# ble2mqtt.net
KiCad netlist of a schematic drawn in EAGLE
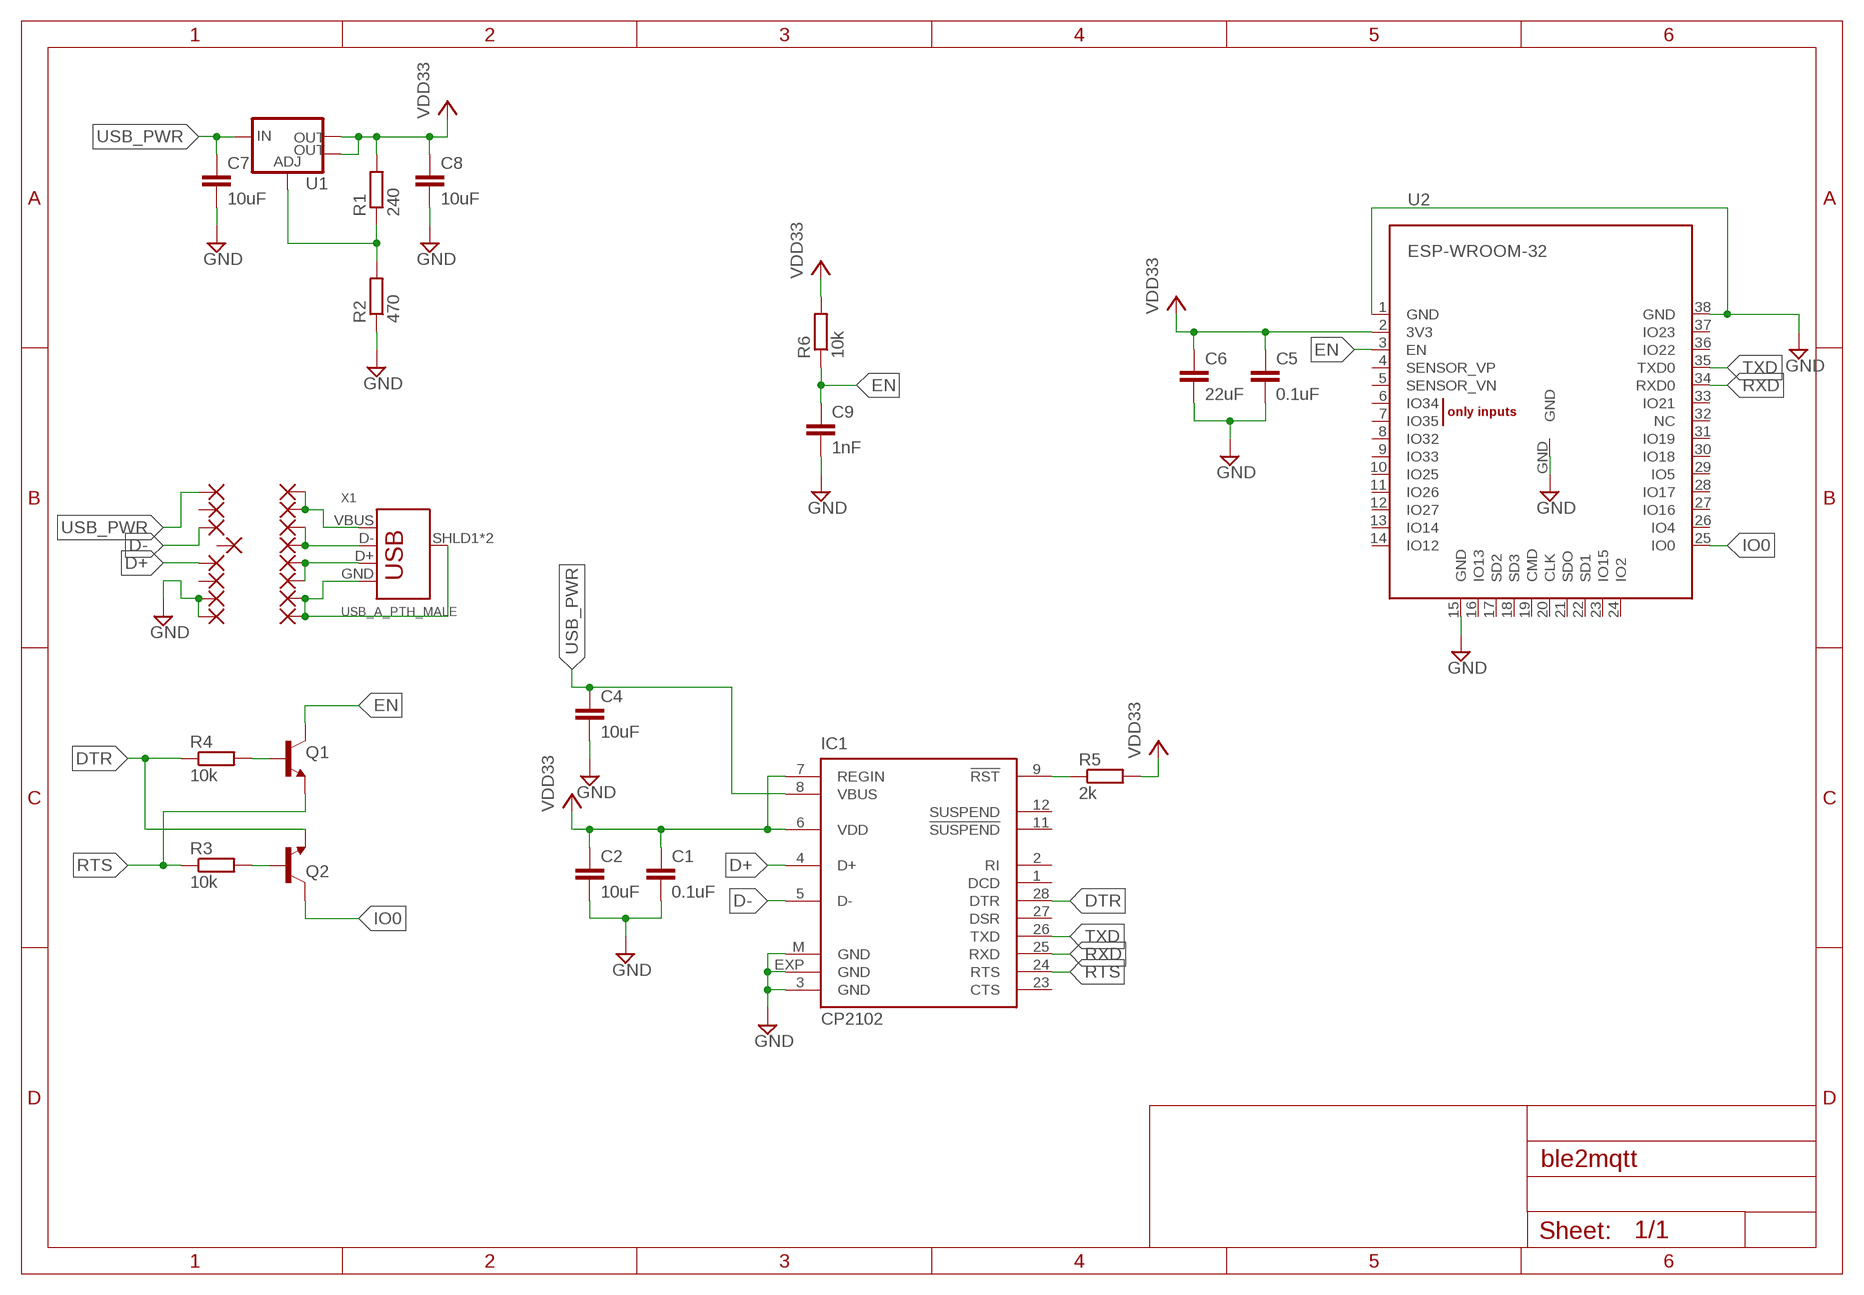
[diagram p0: schematic, sheet 1]

(export (version "E")
  (design (tool "Eeschema 10.0.6"))
  (components
    (comp (ref "C1")
      (value "0.1uF")
      (footprint "eagle-import:0402")
      (libsource (lib "eagle-import") (part "CAPACITOR_0402"))
    )
    (comp (ref "C2")
      (value "10uF")
      (footprint "eagle-import:0402")
      (libsource (lib "eagle-import") (part "CAPACITOR_0402"))
    )
    (comp (ref "C4")
      (value "10uF")
      (footprint "eagle-import:0402")
      (libsource (lib "eagle-import") (part "CAPACITOR_0402"))
    )
    (comp (ref "C5")
      (value "0.1uF")
      (footprint "eagle-import:0402")
      (libsource (lib "eagle-import") (part "CAPACITOR_0402"))
    )
    (comp (ref "C6")
      (value "22uF")
      (footprint "eagle-import:0402")
      (libsource (lib "eagle-import") (part "CAPACITOR_0402"))
    )
    (comp (ref "C7")
      (value "10uF")
      (footprint "eagle-import:0402")
      (libsource (lib "eagle-import") (part "CAPACITOR_0402"))
    )
    (comp (ref "C8")
      (value "10uF")
      (footprint "eagle-import:0402")
      (libsource (lib "eagle-import") (part "CAPACITOR_0402"))
    )
    (comp (ref "C9")
      (value "1nF")
      (footprint "eagle-import:0402")
      (libsource (lib "eagle-import") (part "CAPACITOR_0402"))
    )
    (comp (ref "IC1")
      (value "CP2102")
      (footprint "eagle-import:MLP28")
      (fields (field (name "MF") "FARNELL") (field (name "MPN") "CP2102-GM"))
      (libsource (lib "eagle-import") (part "CP2102"))
    )
    (comp (ref "PAD1")
      (value "WIREPADSMD1,27-254")
      (footprint "eagle-import:SMD1,27-2,54")
      (libsource (lib "eagle-import") (part "WIREPADSMD1,27-254"))
    )
    (comp (ref "PAD2")
      (value "WIREPADSMD1,27-254")
      (footprint "eagle-import:SMD1,27-2,54")
      (libsource (lib "eagle-import") (part "WIREPADSMD1,27-254"))
    )
    (comp (ref "PAD3")
      (value "WIREPADSMD1,27-254")
      (footprint "eagle-import:SMD1,27-2,54")
      (libsource (lib "eagle-import") (part "WIREPADSMD1,27-254"))
    )
    (comp (ref "PAD4")
      (value "WIREPADSMD1,27-254")
      (footprint "eagle-import:SMD1,27-2,54")
      (libsource (lib "eagle-import") (part "WIREPADSMD1,27-254"))
    )
    (comp (ref "PAD5")
      (value "WIREPADSMD1,27-254")
      (footprint "eagle-import:SMD1,27-2,54")
      (libsource (lib "eagle-import") (part "WIREPADSMD1,27-254"))
    )
    (comp (ref "PAD6")
      (value "WIREPADSMD1,27-254")
      (footprint "eagle-import:SMD1,27-2,54")
      (libsource (lib "eagle-import") (part "WIREPADSMD1,27-254"))
    )
    (comp (ref "PAD7")
      (value "WIREPADSMD1,27-254")
      (footprint "eagle-import:SMD1,27-2,54")
      (libsource (lib "eagle-import") (part "WIREPADSMD1,27-254"))
    )
    (comp (ref "PAD8")
      (value "WIREPADSMD1,27-254")
      (footprint "eagle-import:SMD1,27-2,54")
      (libsource (lib "eagle-import") (part "WIREPADSMD1,27-254"))
    )
    (comp (ref "PAD9")
      (value "WIREPADSMD1,27-254")
      (footprint "eagle-import:SMD1,27-2,54")
      (libsource (lib "eagle-import") (part "WIREPADSMD1,27-254"))
    )
    (comp (ref "PAD10")
      (value "WIREPADSMD1,27-254")
      (footprint "eagle-import:SMD1,27-2,54")
      (libsource (lib "eagle-import") (part "WIREPADSMD1,27-254"))
    )
    (comp (ref "PAD11")
      (value "WIREPADSMD1,27-254")
      (footprint "eagle-import:SMD1,27-2,54")
      (libsource (lib "eagle-import") (part "WIREPADSMD1,27-254"))
    )
    (comp (ref "PAD12")
      (value "WIREPADSMD1,27-254")
      (footprint "eagle-import:SMD1,27-2,54")
      (libsource (lib "eagle-import") (part "WIREPADSMD1,27-254"))
    )
    (comp (ref "PAD13")
      (value "WIREPADSMD1,27-254")
      (footprint "eagle-import:SMD1,27-2,54")
      (libsource (lib "eagle-import") (part "WIREPADSMD1,27-254"))
    )
    (comp (ref "PAD14")
      (value "WIREPADSMD1,27-254")
      (footprint "eagle-import:SMD1,27-2,54")
      (libsource (lib "eagle-import") (part "WIREPADSMD1,27-254"))
    )
    (comp (ref "PAD15")
      (value "WIREPADSMD1,27-254")
      (footprint "eagle-import:SMD1,27-2,54")
      (libsource (lib "eagle-import") (part "WIREPADSMD1,27-254"))
    )
    (comp (ref "PAD16")
      (value "WIREPADSMD1,27-254")
      (footprint "eagle-import:SMD1,27-2,54")
      (libsource (lib "eagle-import") (part "WIREPADSMD1,27-254"))
    )
    (comp (ref "Q1")
      (value "TRANS_NPN-MMBT2222AL")
      (footprint "eagle-import:SOT23-3")
      (libsource (lib "eagle-import") (part "TRANS_NPN-MMBT2222AL"))
    )
    (comp (ref "Q2")
      (value "TRANS_NPN-MMBT2222AL")
      (footprint "eagle-import:SOT23-3")
      (libsource (lib "eagle-import") (part "TRANS_NPN-MMBT2222AL"))
    )
    (comp (ref "R1")
      (value "240")
      (footprint "eagle-import:0402")
      (libsource (lib "eagle-import") (part "RESISTOR_0402"))
    )
    (comp (ref "R2")
      (value "470")
      (footprint "eagle-import:0402")
      (libsource (lib "eagle-import") (part "RESISTOR_0402"))
    )
    (comp (ref "R3")
      (value "10k")
      (footprint "eagle-import:0402")
      (libsource (lib "eagle-import") (part "RESISTOR_0402"))
    )
    (comp (ref "R4")
      (value "10k")
      (footprint "eagle-import:0402")
      (libsource (lib "eagle-import") (part "RESISTOR_0402"))
    )
    (comp (ref "R5")
      (value "2k")
      (footprint "eagle-import:0402")
      (libsource (lib "eagle-import") (part "RESISTOR_0402"))
    )
    (comp (ref "R6")
      (value "10k")
      (footprint "eagle-import:0402")
      (libsource (lib "eagle-import") (part "RESISTOR_0402"))
    )
    (comp (ref "U1")
      (value "V_REG_LM1117SOT223")
      (footprint "eagle-import:SOT223")
      (libsource (lib "eagle-import") (part "V_REG_LM1117SOT223"))
    )
    (comp (ref "U2")
      (value "ESP-WROOM-32")
      (footprint "eagle-import:ESP-WROOM-32")
      (libsource (lib "eagle-import") (part "ESP-WROOM-32"))
    )
    (comp (ref "X1")
      (value "USB_A_PTH_MALE")
      (footprint "eagle-import:USB-A-H")
      (libsource (lib "eagle-import") (part "USB_A_PTH_MALE"))
    )
  )
  (nets
    (net (code "1") (name "D+") (class "Default")
      (node (ref "IC1") (pin "4") (pinfunction "D+_4") (pintype "bidirectional"))
      (node (ref "PAD13") (pin "1") (pinfunction "P_1") (pintype "passive"))
    )
    (net (code "2") (name "D-") (class "Default")
      (node (ref "IC1") (pin "5") (pinfunction "D-_5") (pintype "bidirectional"))
      (node (ref "PAD11") (pin "1") (pinfunction "P_1") (pintype "passive"))
    )
    (net (code "3") (name "DTR") (class "Default")
      (node (ref "IC1") (pin "28") (pinfunction "DTR_28") (pintype "output"))
      (node (ref "Q2") (pin "2") (pinfunction "E_2") (pintype "passive"))
      (node (ref "R4") (pin "1") (pinfunction "1_1") (pintype "passive"))
    )
    (net (code "4") (name "EN") (class "Default")
      (node (ref "C9") (pin "1") (pinfunction "1_1") (pintype "passive"))
      (node (ref "Q1") (pin "3") (pinfunction "C_3") (pintype "passive"))
      (node (ref "R6") (pin "1") (pinfunction "1_1") (pintype "passive"))
      (node (ref "U2") (pin "3") (pinfunction "EN_3") (pintype "bidirectional"))
    )
    (net (code "5") (name "GND") (class "Default")
      (node (ref "C1") (pin "2") (pinfunction "2_2") (pintype "passive"))
      (node (ref "C2") (pin "2") (pinfunction "2_2") (pintype "passive"))
      (node (ref "C4") (pin "2") (pinfunction "2_2") (pintype "passive"))
      (node (ref "C5") (pin "2") (pinfunction "2_2") (pintype "passive"))
      (node (ref "C6") (pin "2") (pinfunction "2_2") (pintype "passive"))
      (node (ref "C7") (pin "2") (pinfunction "2_2") (pintype "passive"))
      (node (ref "C8") (pin "2") (pinfunction "2_2") (pintype "passive"))
      (node (ref "C9") (pin "2") (pinfunction "2_2") (pintype "passive"))
      (node (ref "IC1") (pin "3") (pinfunction "GND_3") (pintype "power_in"))
      (node (ref "IC1") (pin "EXP") (pinfunction "GND_EXP") (pintype "power_in"))
      (node (ref "IC1") (pin "M") (pinfunction "GND_M") (pintype "power_in"))
      (node (ref "PAD15") (pin "1") (pinfunction "P_1") (pintype "passive"))
      (node (ref "PAD16") (pin "1") (pinfunction "P_1") (pintype "passive"))
      (node (ref "R2") (pin "1") (pinfunction "1_1") (pintype "passive"))
      (node (ref "U2") (pin "1") (pinfunction "GND_1") (pintype "bidirectional"))
      (node (ref "U2") (pin "15") (pinfunction "GND_15") (pintype "bidirectional"))
      (node (ref "U2") (pin "38") (pinfunction "GND_38") (pintype "bidirectional"))
      (node (ref "U2") (pin "GND") (pinfunction "GND_GND") (pintype "bidirectional"))
    )
    (net (code "6") (name "IO0") (class "Default")
      (node (ref "Q2") (pin "3") (pinfunction "C_3") (pintype "passive"))
      (node (ref "U2") (pin "25") (pinfunction "IO0_25") (pintype "bidirectional"))
    )
    (net (code "7") (name "Net-(IC1-~{RST})") (class "Default")
      (node (ref "IC1") (pin "9") (pinfunction "~{RST}_9") (pintype "bidirectional"))
      (node (ref "R5") (pin "1") (pinfunction "1_1") (pintype "passive"))
    )
    (net (code "8") (name "Net-(PAD1-P)") (class "Default")
      (node (ref "PAD1") (pin "1") (pinfunction "P_1") (pintype "passive"))
      (node (ref "PAD2") (pin "1") (pinfunction "P_1") (pintype "passive"))
      (node (ref "X1") (pin "VBUS") (pinfunction "VBUS_VBUS") (pintype "power_in"))
    )
    (net (code "9") (name "Net-(PAD3-P)") (class "Default")
      (node (ref "PAD3") (pin "1") (pinfunction "P_1") (pintype "passive"))
      (node (ref "PAD4") (pin "1") (pinfunction "P_1") (pintype "passive"))
      (node (ref "X1") (pin "D-") (pinfunction "D-_D-") (pintype "bidirectional"))
    )
    (net (code "10") (name "Net-(PAD5-P)") (class "Default")
      (node (ref "PAD5") (pin "1") (pinfunction "P_1") (pintype "passive"))
      (node (ref "PAD6") (pin "1") (pinfunction "P_1") (pintype "passive"))
      (node (ref "X1") (pin "D+") (pinfunction "D+_D+") (pintype "bidirectional"))
    )
    (net (code "11") (name "Net-(PAD7-P)") (class "Default")
      (node (ref "PAD7") (pin "1") (pinfunction "P_1") (pintype "passive"))
      (node (ref "PAD8") (pin "1") (pinfunction "P_1") (pintype "passive"))
      (node (ref "X1") (pin "GND") (pinfunction "GND_GND") (pintype "power_in"))
      (node (ref "X1") (pin "SHLD1") (pinfunction "SHIELD_SHLD1") (pintype "bidirectional"))
      (node (ref "X1") (pin "SHLD2") (pinfunction "SHIELD_SHLD2") (pintype "bidirectional"))
    )
    (net (code "12") (name "Net-(Q1-B)") (class "Default")
      (node (ref "Q1") (pin "1") (pinfunction "B_1") (pintype "passive"))
      (node (ref "R4") (pin "2") (pinfunction "2_2") (pintype "passive"))
    )
    (net (code "13") (name "Net-(Q2-B)") (class "Default")
      (node (ref "Q2") (pin "1") (pinfunction "B_1") (pintype "passive"))
      (node (ref "R3") (pin "2") (pinfunction "2_2") (pintype "passive"))
    )
    (net (code "14") (name "Net-(U1-ADJ)") (class "Default")
      (node (ref "R1") (pin "1") (pinfunction "1_1") (pintype "passive"))
      (node (ref "R2") (pin "2") (pinfunction "2_2") (pintype "passive"))
      (node (ref "U1") (pin "1") (pinfunction "ADJ_1") (pintype "input"))
    )
    (net (code "15") (name "RTS") (class "Default")
      (node (ref "IC1") (pin "24") (pinfunction "RTS_24") (pintype "output"))
      (node (ref "Q1") (pin "2") (pinfunction "E_2") (pintype "passive"))
      (node (ref "R3") (pin "1") (pinfunction "1_1") (pintype "passive"))
    )
    (net (code "16") (name "RXD") (class "Default")
      (node (ref "IC1") (pin "25") (pinfunction "RXD_25") (pintype "input"))
      (node (ref "U2") (pin "34") (pinfunction "RXD0_34") (pintype "bidirectional"))
    )
    (net (code "17") (name "TXD") (class "Default")
      (node (ref "IC1") (pin "26") (pinfunction "TXD_26") (pintype "output"))
      (node (ref "U2") (pin "35") (pinfunction "TXD0_35") (pintype "bidirectional"))
    )
    (net (code "18") (name "USB_PWR") (class "Default")
      (node (ref "C4") (pin "1") (pinfunction "1_1") (pintype "passive"))
      (node (ref "C7") (pin "1") (pinfunction "1_1") (pintype "passive"))
      (node (ref "IC1") (pin "8") (pinfunction "VBUS_8") (pintype "input"))
      (node (ref "PAD9") (pin "1") (pinfunction "P_1") (pintype "passive"))
      (node (ref "U1") (pin "3") (pinfunction "IN_3") (pintype "input"))
    )
    (net (code "19") (name "VDD33") (class "Default")
      (node (ref "C1") (pin "1") (pinfunction "1_1") (pintype "passive"))
      (node (ref "C2") (pin "1") (pinfunction "1_1") (pintype "passive"))
      (node (ref "C5") (pin "1") (pinfunction "1_1") (pintype "passive"))
      (node (ref "C6") (pin "1") (pinfunction "1_1") (pintype "passive"))
      (node (ref "C8") (pin "1") (pinfunction "1_1") (pintype "passive"))
      (node (ref "IC1") (pin "6") (pinfunction "VDD_6") (pintype "power_in"))
      (node (ref "IC1") (pin "7") (pinfunction "REGIN_7") (pintype "passive"))
      (node (ref "R1") (pin "2") (pinfunction "2_2") (pintype "passive"))
      (node (ref "R5") (pin "2") (pinfunction "2_2") (pintype "passive"))
      (node (ref "R6") (pin "2") (pinfunction "2_2") (pintype "passive"))
      (node (ref "U1") (pin "2") (pinfunction "OUT_2") (pintype "output"))
      (node (ref "U1") (pin "4") (pinfunction "OUT_4") (pintype "output"))
      (node (ref "U2") (pin "2") (pinfunction "3V3_2") (pintype "bidirectional"))
    )
    (net (code "20") (name "unconnected-(IC1-CTS-Pad23)") (class "Default")
      (node (ref "IC1") (pin "23") (pinfunction "CTS_23") (pintype "input"))
    )
    (net (code "21") (name "unconnected-(IC1-DCD-Pad1)") (class "Default")
      (node (ref "IC1") (pin "1") (pinfunction "DCD_1") (pintype "input"))
    )
    (net (code "22") (name "unconnected-(IC1-DSR-Pad27)") (class "Default")
      (node (ref "IC1") (pin "27") (pinfunction "DSR_27") (pintype "input"))
    )
    (net (code "23") (name "unconnected-(IC1-RI-Pad2)") (class "Default")
      (node (ref "IC1") (pin "2") (pinfunction "RI_2") (pintype "input"))
    )
    (net (code "24") (name "unconnected-(IC1-SUSPEND-Pad12)") (class "Default")
      (node (ref "IC1") (pin "12") (pinfunction "SUSPEND_12") (pintype "output"))
    )
    (net (code "25") (name "unconnected-(IC1-~{SUSPEND}-Pad11)") (class "Default")
      (node (ref "IC1") (pin "11") (pinfunction "~{SUSPEND}_11") (pintype "output"))
    )
    (net (code "26") (name "unconnected-(PAD10-P-Pad1)") (class "Default")
      (node (ref "PAD10") (pin "1") (pinfunction "P_1") (pintype "passive"))
    )
    (net (code "27") (name "unconnected-(PAD12-P-Pad1)") (class "Default")
      (node (ref "PAD12") (pin "1") (pinfunction "P_1") (pintype "passive"))
    )
    (net (code "28") (name "unconnected-(PAD14-P-Pad1)") (class "Default")
      (node (ref "PAD14") (pin "1") (pinfunction "P_1") (pintype "passive"))
    )
    (net (code "29") (name "unconnected-(U2-CLK-Pad20)") (class "Default")
      (node (ref "U2") (pin "20") (pinfunction "CLK_20") (pintype "bidirectional"))
    )
    (net (code "30") (name "unconnected-(U2-CMD-Pad19)") (class "Default")
      (node (ref "U2") (pin "19") (pinfunction "CMD_19") (pintype "bidirectional"))
    )
    (net (code "31") (name "unconnected-(U2-IO2-Pad24)") (class "Default")
      (node (ref "U2") (pin "24") (pinfunction "IO2_24") (pintype "bidirectional"))
    )
    (net (code "32") (name "unconnected-(U2-IO4-Pad26)") (class "Default")
      (node (ref "U2") (pin "26") (pinfunction "IO4_26") (pintype "bidirectional"))
    )
    (net (code "33") (name "unconnected-(U2-IO5-Pad29)") (class "Default")
      (node (ref "U2") (pin "29") (pinfunction "IO5_29") (pintype "bidirectional"))
    )
    (net (code "34") (name "unconnected-(U2-IO12-Pad14)") (class "Default")
      (node (ref "U2") (pin "14") (pinfunction "IO12_14") (pintype "bidirectional"))
    )
    (net (code "35") (name "unconnected-(U2-IO13-Pad16)") (class "Default")
      (node (ref "U2") (pin "16") (pinfunction "IO13_16") (pintype "bidirectional"))
    )
    (net (code "36") (name "unconnected-(U2-IO14-Pad13)") (class "Default")
      (node (ref "U2") (pin "13") (pinfunction "IO14_13") (pintype "bidirectional"))
    )
    (net (code "37") (name "unconnected-(U2-IO15-Pad23)") (class "Default")
      (node (ref "U2") (pin "23") (pinfunction "IO15_23") (pintype "bidirectional"))
    )
    (net (code "38") (name "unconnected-(U2-IO16-Pad27)") (class "Default")
      (node (ref "U2") (pin "27") (pinfunction "IO16_27") (pintype "bidirectional"))
    )
    (net (code "39") (name "unconnected-(U2-IO17-Pad28)") (class "Default")
      (node (ref "U2") (pin "28") (pinfunction "IO17_28") (pintype "bidirectional"))
    )
    (net (code "40") (name "unconnected-(U2-IO18-Pad30)") (class "Default")
      (node (ref "U2") (pin "30") (pinfunction "IO18_30") (pintype "bidirectional"))
    )
    (net (code "41") (name "unconnected-(U2-IO19-Pad31)") (class "Default")
      (node (ref "U2") (pin "31") (pinfunction "IO19_31") (pintype "bidirectional"))
    )
    (net (code "42") (name "unconnected-(U2-IO21-Pad33)") (class "Default")
      (node (ref "U2") (pin "33") (pinfunction "IO21_33") (pintype "bidirectional"))
    )
    (net (code "43") (name "unconnected-(U2-IO22-Pad36)") (class "Default")
      (node (ref "U2") (pin "36") (pinfunction "IO22_36") (pintype "bidirectional"))
    )
    (net (code "44") (name "unconnected-(U2-IO23-Pad37)") (class "Default")
      (node (ref "U2") (pin "37") (pinfunction "IO23_37") (pintype "bidirectional"))
    )
    (net (code "45") (name "unconnected-(U2-IO25-Pad10)") (class "Default")
      (node (ref "U2") (pin "10") (pinfunction "IO25_10") (pintype "bidirectional"))
    )
    (net (code "46") (name "unconnected-(U2-IO26-Pad11)") (class "Default")
      (node (ref "U2") (pin "11") (pinfunction "IO26_11") (pintype "bidirectional"))
    )
    (net (code "47") (name "unconnected-(U2-IO27-Pad12)") (class "Default")
      (node (ref "U2") (pin "12") (pinfunction "IO27_12") (pintype "bidirectional"))
    )
    (net (code "48") (name "unconnected-(U2-IO32-Pad8)") (class "Default")
      (node (ref "U2") (pin "8") (pinfunction "IO32_8") (pintype "bidirectional"))
    )
    (net (code "49") (name "unconnected-(U2-IO33-Pad9)") (class "Default")
      (node (ref "U2") (pin "9") (pinfunction "IO33_9") (pintype "bidirectional"))
    )
    (net (code "50") (name "unconnected-(U2-IO34-Pad6)") (class "Default")
      (node (ref "U2") (pin "6") (pinfunction "IO34_6") (pintype "input"))
    )
    (net (code "51") (name "unconnected-(U2-IO35-Pad7)") (class "Default")
      (node (ref "U2") (pin "7") (pinfunction "IO35_7") (pintype "input"))
    )
    (net (code "52") (name "unconnected-(U2-NC-Pad32)") (class "Default")
      (node (ref "U2") (pin "32") (pinfunction "NC_32") (pintype "bidirectional"))
    )
    (net (code "53") (name "unconnected-(U2-SD1-Pad22)") (class "Default")
      (node (ref "U2") (pin "22") (pinfunction "SD1_22") (pintype "bidirectional"))
    )
    (net (code "54") (name "unconnected-(U2-SD2-Pad17)") (class "Default")
      (node (ref "U2") (pin "17") (pinfunction "SD2_17") (pintype "bidirectional"))
    )
    (net (code "55") (name "unconnected-(U2-SD3-Pad18)") (class "Default")
      (node (ref "U2") (pin "18") (pinfunction "SD3_18") (pintype "bidirectional"))
    )
    (net (code "56") (name "unconnected-(U2-SDO-Pad21)") (class "Default")
      (node (ref "U2") (pin "21") (pinfunction "SDO_21") (pintype "bidirectional"))
    )
    (net (code "57") (name "unconnected-(U2-SENSOR_VN-Pad5)") (class "Default")
      (node (ref "U2") (pin "5") (pinfunction "SENSOR_VN_5") (pintype "input"))
    )
    (net (code "58") (name "unconnected-(U2-SENSOR_VP-Pad4)") (class "Default")
      (node (ref "U2") (pin "4") (pinfunction "SENSOR_VP_4") (pintype "input"))
    )
  )
)
